# ESP32_breakout.net
KiCad netlist of a schematic drawn in EAGLE
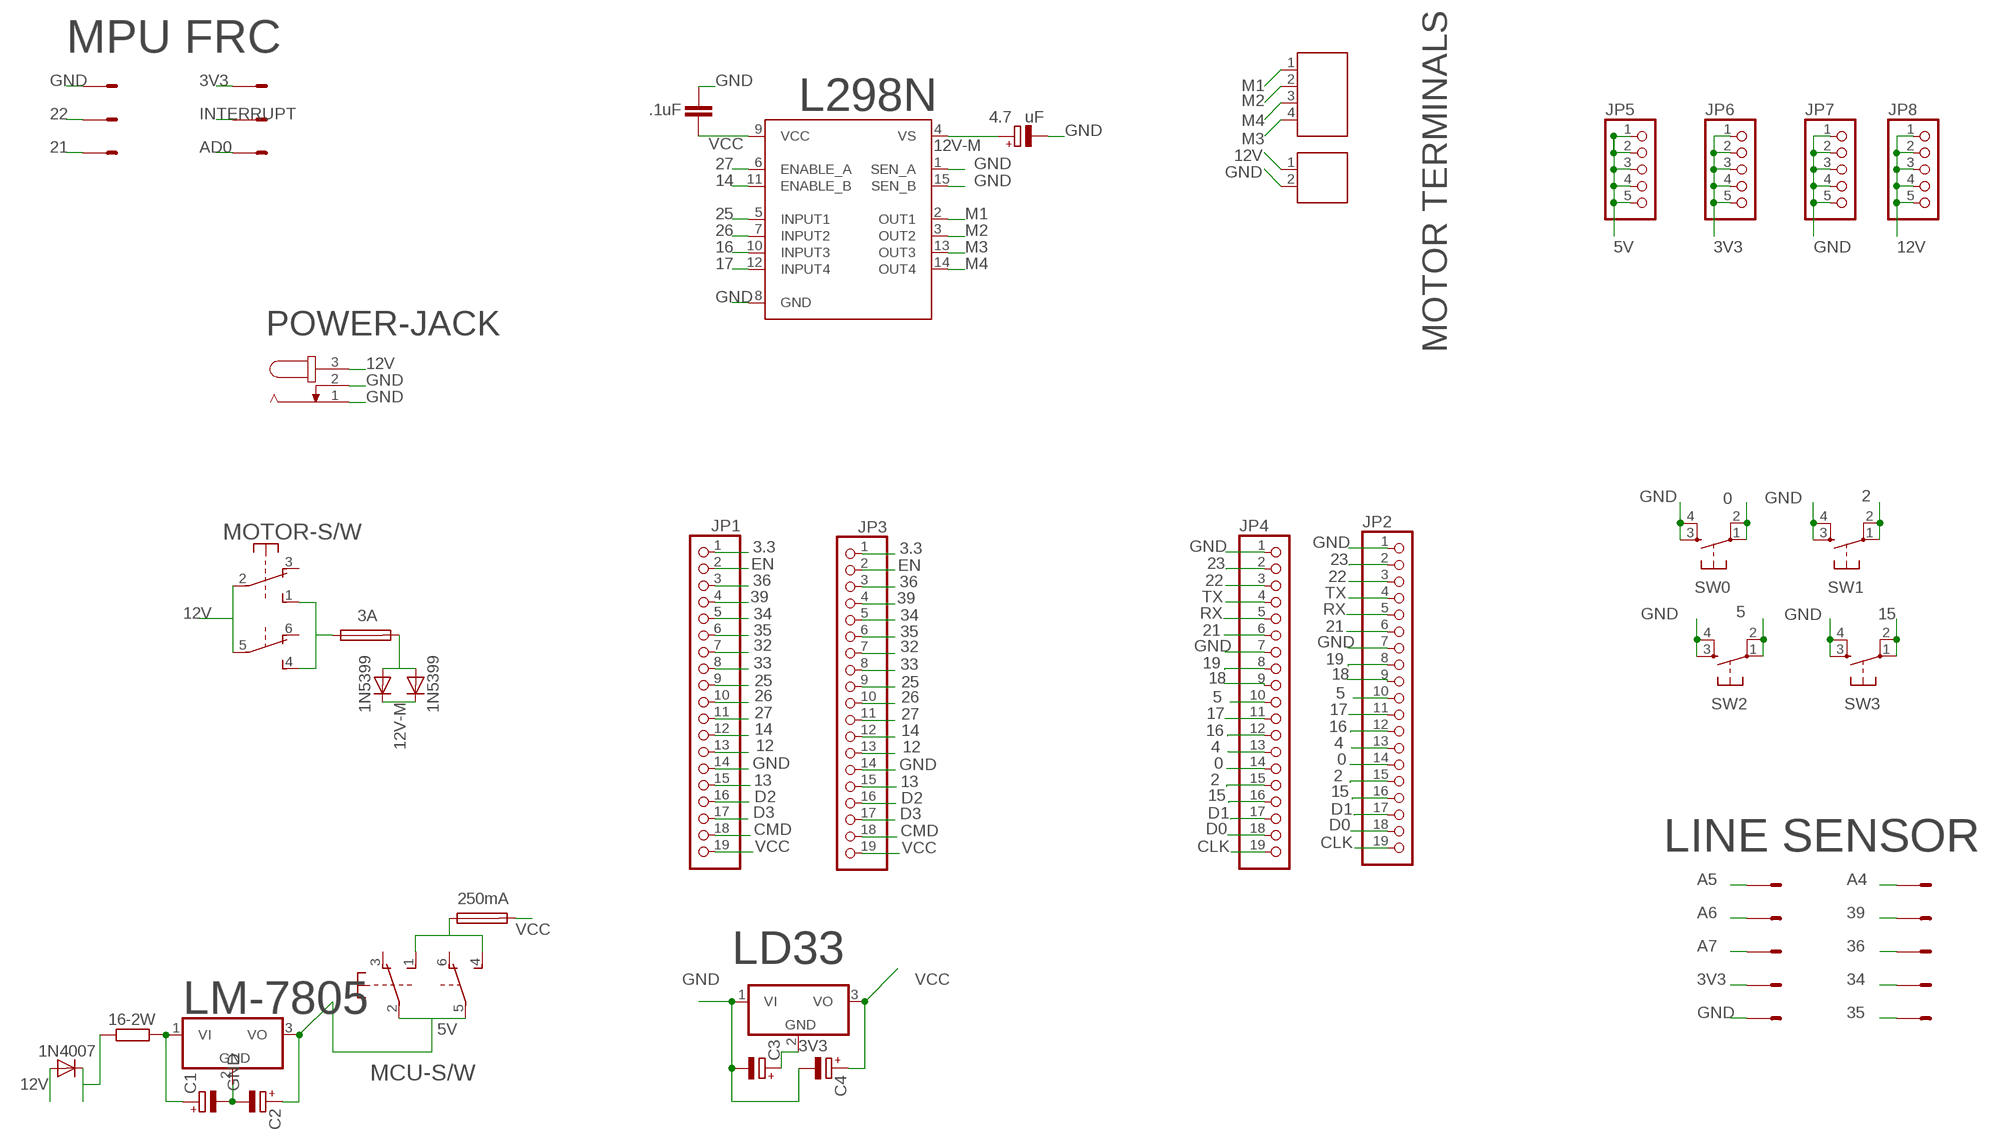
[diagram p0: schematic, sheet 1]

(export (version "E")
  (design (tool "Eeschema 10.0.6"))
  (components
    (comp (ref "12V")
      (value "691131710002")
      (footprint "eagle-import:691131710002")
      (libsource (lib "eagle-import") (part "691131710002"))
    )
    (comp (ref "16-2W")
      (value "R-EU_0617/17")
      (footprint "eagle-import:0617_17")
      (libsource (lib "eagle-import") (part "R-EU_0617/17"))
    )
    (comp (ref "C1")
      (value "CPOL-EUE2.5-6")
      (footprint "eagle-import:E2,5-6")
      (libsource (lib "eagle-import") (part "rcl_334_CPOL-EUE2.5-6"))
    )
    (comp (ref "C2")
      (value "CPOL-EUE2.5-6")
      (footprint "eagle-import:E2,5-6")
      (libsource (lib "eagle-import") (part "rcl_334_CPOL-EUE2.5-6"))
    )
    (comp (ref "C3")
      (value "CPOL-EUE2.5-6")
      (footprint "eagle-import:E2,5-6")
      (libsource (lib "eagle-import") (part "rcl_334_CPOL-EUE2.5-6"))
    )
    (comp (ref "C4")
      (value "CPOL-EUE2.5-6")
      (footprint "eagle-import:E2,5-6")
      (libsource (lib "eagle-import") (part "rcl_334_CPOL-EUE2.5-6"))
    )
    (comp (ref "C8")
      (value "4.7 uF")
      (footprint "eagle-import:E2,5-6")
      (libsource (lib "eagle-import") (part "CPOL-EUE2.5-6"))
    )
    (comp (ref "C9")
      (value ".1uF")
      (footprint "eagle-import:C5B2.5")
      (libsource (lib "eagle-import") (part "C5/2.5"))
    )
    (comp (ref "D4")
      (value "1N4007")
      (footprint "eagle-import:D-7.5")
      (libsource (lib "eagle-import") (part "DIODE-D-7.5"))
    )
    (comp (ref "D6")
      (value "1N5399")
      (footprint "eagle-import:DO15-12")
      (libsource (lib "eagle-import") (part "DIODE-DO15-12"))
    )
    (comp (ref "D7")
      (value "1N5399")
      (footprint "eagle-import:DO15-12")
      (libsource (lib "eagle-import") (part "DIODE-DO15-12"))
    )
    (comp (ref "F1")
      (value "3A")
      (footprint "eagle-import:SH25")
      (fields (field (name "MF") "SCHURTER") (field (name "MPN") "0031.8211"))
      (libsource (lib "eagle-import") (part "SH25"))
    )
    (comp (ref "F2")
      (value "250mA")
      (footprint "eagle-import:SH25")
      (fields (field (name "MF") "SCHURTER") (field (name "MPN") "0031.8211"))
      (libsource (lib "eagle-import") (part "SH25"))
    )
    (comp (ref "J1")
      (value "691131710004")
      (footprint "eagle-import:691131710004")
      (libsource (lib "eagle-import") (part "691131710004"))
    )
    (comp (ref "JP1")
      (value "PINHD-1X19")
      (footprint "eagle-import:1X19")
      (libsource (lib "eagle-import") (part "PINHD-1X19"))
    )
    (comp (ref "JP2")
      (value "PINHD-1X19")
      (footprint "eagle-import:1X19")
      (libsource (lib "eagle-import") (part "PINHD-1X19"))
    )
    (comp (ref "JP3")
      (value "PINHD-1X19")
      (footprint "eagle-import:1X19")
      (libsource (lib "eagle-import") (part "PINHD-1X19"))
    )
    (comp (ref "JP4")
      (value "PINHD-1X19")
      (footprint "eagle-import:1X19")
      (libsource (lib "eagle-import") (part "PINHD-1X19"))
    )
    (comp (ref "JP5")
      (value "PINHD-1X5")
      (footprint "eagle-import:1X05")
      (libsource (lib "eagle-import") (part "PINHD-1X5"))
    )
    (comp (ref "JP6")
      (value "PINHD-1X5")
      (footprint "eagle-import:1X05")
      (libsource (lib "eagle-import") (part "PINHD-1X5"))
    )
    (comp (ref "JP7")
      (value "PINHD-1X5")
      (footprint "eagle-import:1X05")
      (libsource (lib "eagle-import") (part "PINHD-1X5"))
    )
    (comp (ref "JP8")
      (value "PINHD-1X5")
      (footprint "eagle-import:1X05")
      (libsource (lib "eagle-import") (part "PINHD-1X5"))
    )
    (comp (ref "L298N")
      (value "L298")
      (footprint "eagle-import:MULTIWATT-15")
      (fields (field (name "MPN") "L298N"))
      (libsource (lib "eagle-import") (part "L298"))
    )
    (comp (ref "LD33")
      (value "786TV")
      (footprint "eagle-import:TO220V")
      (libsource (lib "eagle-import") (part "78TV6"))
    )
    (comp (ref "LINE-SENSOR")
      (value "057-010-1")
      (footprint "eagle-import:057-010-1")
      (libsource (lib "eagle-import") (part "057-010-1"))
    )
    (comp (ref "LM-7805")
      (value "786TV")
      (footprint "eagle-import:TO220V")
      (libsource (lib "eagle-import") (part "78TV6"))
    )
    (comp (ref "MCU-S/W")
      (value "9077-2")
      (footprint "eagle-import:9077-2")
      (libsource (lib "eagle-import") (part "9077-2"))
    )
    (comp (ref "MOTOR-S/W")
      (value "9077-2")
      (footprint "eagle-import:9077-2")
      (libsource (lib "eagle-import") (part "9077-2"))
    )
    (comp (ref "MPU-6050")
      (value "057-006-1")
      (footprint "eagle-import:057-006-1")
      (libsource (lib "eagle-import") (part "057-006-1"))
    )
    (comp (ref "POWER-JACK")
      (value "JACK-PLUG1")
      (footprint "eagle-import:SPC4078")
      (libsource (lib "eagle-import") (part "JACK-PLUG1"))
    )
    (comp (ref "SW0")
      (value "DTS-6")
      (footprint "eagle-import:DTS-6")
      (libsource (lib "eagle-import") (part "DTS-6"))
    )
    (comp (ref "SW1")
      (value "DTS-6")
      (footprint "eagle-import:DTS-6")
      (libsource (lib "eagle-import") (part "DTS-6"))
    )
    (comp (ref "SW2")
      (value "DTS-6")
      (footprint "eagle-import:DTS-6")
      (libsource (lib "eagle-import") (part "DTS-6"))
    )
    (comp (ref "SW3")
      (value "DTS-6")
      (footprint "eagle-import:DTS-6")
      (libsource (lib "eagle-import") (part "DTS-6"))
    )
  )
  (nets
    (net (code "1") (name "/0") (class "Default")
      (node (ref "JP2") (pin "14") (pinfunction "14_14") (pintype "passive"))
      (node (ref "JP4") (pin "14") (pinfunction "14_14") (pintype "passive"))
      (node (ref "SW0") (pin "1") (pinfunction "1_1") (pintype "passive"))
      (node (ref "SW0") (pin "2") (pinfunction "2_2") (pintype "passive"))
    )
    (net (code "2") (name "/2") (class "Default")
      (node (ref "JP2") (pin "15") (pinfunction "15_15") (pintype "passive"))
      (node (ref "JP4") (pin "15") (pinfunction "15_15") (pintype "passive"))
      (node (ref "SW1") (pin "1") (pinfunction "1_1") (pintype "passive"))
      (node (ref "SW1") (pin "2") (pinfunction "2_2") (pintype "passive"))
    )
    (net (code "3") (name "/3.3") (class "Default")
      (node (ref "JP1") (pin "1") (pinfunction "1_1") (pintype "passive"))
      (node (ref "JP3") (pin "1") (pinfunction "1_1") (pintype "passive"))
    )
    (net (code "4") (name "/3V3") (class "Default")
      (node (ref "C3") (pin "+") (pinfunction "+_+") (pintype "passive"))
      (node (ref "JP6") (pin "1") (pinfunction "1_1") (pintype "passive"))
      (node (ref "JP6") (pin "2") (pinfunction "2_2") (pintype "passive"))
      (node (ref "JP6") (pin "3") (pinfunction "3_3") (pintype "passive"))
      (node (ref "JP6") (pin "4") (pinfunction "4_4") (pintype "passive"))
      (node (ref "JP6") (pin "5") (pinfunction "5_5") (pintype "passive"))
      (node (ref "LD33") (pin "2") (pinfunction "GND_2") (pintype "passive"))
      (node (ref "LINE-SENSOR") (pin "7") (pinfunction "S_7") (pintype "passive"))
      (node (ref "MPU-6050") (pin "2") (pinfunction "S_2") (pintype "passive"))
    )
    (net (code "5") (name "/4") (class "Default")
      (node (ref "JP2") (pin "13") (pinfunction "13_13") (pintype "passive"))
      (node (ref "JP4") (pin "13") (pinfunction "13_13") (pintype "passive"))
    )
    (net (code "6") (name "/5") (class "Default")
      (node (ref "JP2") (pin "10") (pinfunction "10_10") (pintype "passive"))
      (node (ref "JP4") (pin "10") (pinfunction "10_10") (pintype "passive"))
      (node (ref "SW2") (pin "1") (pinfunction "1_1") (pintype "passive"))
      (node (ref "SW2") (pin "2") (pinfunction "2_2") (pintype "passive"))
    )
    (net (code "7") (name "/5V") (class "Default")
      (node (ref "C2") (pin "+") (pinfunction "+_+") (pintype "passive"))
      (node (ref "JP5") (pin "1") (pinfunction "1_1") (pintype "passive"))
      (node (ref "JP5") (pin "2") (pinfunction "2_2") (pintype "passive"))
      (node (ref "JP5") (pin "3") (pinfunction "3_3") (pintype "passive"))
      (node (ref "JP5") (pin "4") (pinfunction "4_4") (pintype "passive"))
      (node (ref "JP5") (pin "5") (pinfunction "5_5") (pintype "passive"))
      (node (ref "LM-7805") (pin "3") (pinfunction "VO_3") (pintype "passive"))
      (node (ref "MCU-S/W") (pin "2") (pinfunction "P_2") (pintype "passive"))
      (node (ref "MCU-S/W") (pin "5") (pinfunction "P_5") (pintype "passive"))
    )
    (net (code "8") (name "/12") (class "Default")
      (node (ref "JP1") (pin "13") (pinfunction "13_13") (pintype "passive"))
      (node (ref "JP3") (pin "13") (pinfunction "13_13") (pintype "passive"))
    )
    (net (code "9") (name "/12V") (class "Default")
      (node (ref "12V") (pin "1") (pinfunction "1_1") (pintype "passive"))
      (node (ref "D4") (pin "A") (pinfunction "A_A") (pintype "passive"))
      (node (ref "JP8") (pin "1") (pinfunction "1_1") (pintype "passive"))
      (node (ref "JP8") (pin "2") (pinfunction "2_2") (pintype "passive"))
      (node (ref "JP8") (pin "3") (pinfunction "3_3") (pintype "passive"))
      (node (ref "JP8") (pin "4") (pinfunction "4_4") (pintype "passive"))
      (node (ref "JP8") (pin "5") (pinfunction "5_5") (pintype "passive"))
      (node (ref "MOTOR-S/W") (pin "2") (pinfunction "P_2") (pintype "passive"))
      (node (ref "MOTOR-S/W") (pin "5") (pinfunction "P_5") (pintype "passive"))
      (node (ref "POWER-JACK") (pin "3") (pinfunction "3_3") (pintype "passive"))
    )
    (net (code "10") (name "/12V-M") (class "Default")
      (node (ref "C8") (pin "+") (pinfunction "+_+") (pintype "passive"))
      (node (ref "D6") (pin "C") (pinfunction "C_C") (pintype "passive"))
      (node (ref "D7") (pin "C") (pinfunction "C_C") (pintype "passive"))
      (node (ref "L298N") (pin "4") (pinfunction "VS_4") (pintype "power_in"))
    )
    (net (code "11") (name "/13") (class "Default")
      (node (ref "JP1") (pin "15") (pinfunction "15_15") (pintype "passive"))
      (node (ref "JP3") (pin "15") (pinfunction "15_15") (pintype "passive"))
    )
    (net (code "12") (name "/14") (class "Default")
      (node (ref "JP1") (pin "12") (pinfunction "12_12") (pintype "passive"))
      (node (ref "JP3") (pin "12") (pinfunction "12_12") (pintype "passive"))
      (node (ref "L298N") (pin "11") (pinfunction "ENABLE_B_11") (pintype "input"))
    )
    (net (code "13") (name "/15") (class "Default")
      (node (ref "JP2") (pin "16") (pinfunction "16_16") (pintype "passive"))
      (node (ref "JP4") (pin "16") (pinfunction "16_16") (pintype "passive"))
      (node (ref "SW3") (pin "1") (pinfunction "1_1") (pintype "passive"))
      (node (ref "SW3") (pin "2") (pinfunction "2_2") (pintype "passive"))
    )
    (net (code "14") (name "/16") (class "Default")
      (node (ref "JP2") (pin "12") (pinfunction "12_12") (pintype "passive"))
      (node (ref "JP4") (pin "12") (pinfunction "12_12") (pintype "passive"))
      (node (ref "L298N") (pin "10") (pinfunction "INPUT3_10") (pintype "input"))
    )
    (net (code "15") (name "/17") (class "Default")
      (node (ref "JP2") (pin "11") (pinfunction "11_11") (pintype "passive"))
      (node (ref "JP4") (pin "11") (pinfunction "11_11") (pintype "passive"))
      (node (ref "L298N") (pin "12") (pinfunction "INPUT4_12") (pintype "input"))
    )
    (net (code "16") (name "/18") (class "Default")
      (node (ref "JP2") (pin "9") (pinfunction "9_9") (pintype "passive"))
      (node (ref "JP4") (pin "9") (pinfunction "9_9") (pintype "passive"))
    )
    (net (code "17") (name "/19") (class "Default")
      (node (ref "JP2") (pin "8") (pinfunction "8_8") (pintype "passive"))
      (node (ref "JP4") (pin "8") (pinfunction "8_8") (pintype "passive"))
    )
    (net (code "18") (name "/21") (class "Default")
      (node (ref "JP2") (pin "6") (pinfunction "6_6") (pintype "passive"))
      (node (ref "JP4") (pin "6") (pinfunction "6_6") (pintype "passive"))
      (node (ref "MPU-6050") (pin "5") (pinfunction "S_5") (pintype "passive"))
    )
    (net (code "19") (name "/22") (class "Default")
      (node (ref "JP2") (pin "3") (pinfunction "3_3") (pintype "passive"))
      (node (ref "JP4") (pin "3") (pinfunction "3_3") (pintype "passive"))
      (node (ref "MPU-6050") (pin "3") (pinfunction "S_3") (pintype "passive"))
    )
    (net (code "20") (name "/23") (class "Default")
      (node (ref "JP2") (pin "2") (pinfunction "2_2") (pintype "passive"))
      (node (ref "JP4") (pin "2") (pinfunction "2_2") (pintype "passive"))
    )
    (net (code "21") (name "/25") (class "Default")
      (node (ref "JP1") (pin "9") (pinfunction "9_9") (pintype "passive"))
      (node (ref "JP3") (pin "9") (pinfunction "9_9") (pintype "passive"))
      (node (ref "L298N") (pin "5") (pinfunction "INPUT1_5") (pintype "input"))
    )
    (net (code "22") (name "/26") (class "Default")
      (node (ref "JP1") (pin "10") (pinfunction "10_10") (pintype "passive"))
      (node (ref "JP3") (pin "10") (pinfunction "10_10") (pintype "passive"))
      (node (ref "L298N") (pin "7") (pinfunction "INPUT2_7") (pintype "input"))
    )
    (net (code "23") (name "/27") (class "Default")
      (node (ref "JP1") (pin "11") (pinfunction "11_11") (pintype "passive"))
      (node (ref "JP3") (pin "11") (pinfunction "11_11") (pintype "passive"))
      (node (ref "L298N") (pin "6") (pinfunction "ENABLE_A_6") (pintype "input"))
    )
    (net (code "24") (name "/32") (class "Default")
      (node (ref "JP1") (pin "7") (pinfunction "7_7") (pintype "passive"))
      (node (ref "JP3") (pin "7") (pinfunction "7_7") (pintype "passive"))
    )
    (net (code "25") (name "/33") (class "Default")
      (node (ref "JP1") (pin "8") (pinfunction "8_8") (pintype "passive"))
      (node (ref "JP3") (pin "8") (pinfunction "8_8") (pintype "passive"))
    )
    (net (code "26") (name "/34") (class "Default")
      (node (ref "JP1") (pin "5") (pinfunction "5_5") (pintype "passive"))
      (node (ref "JP3") (pin "5") (pinfunction "5_5") (pintype "passive"))
      (node (ref "LINE-SENSOR") (pin "8") (pinfunction "S_8") (pintype "passive"))
    )
    (net (code "27") (name "/35") (class "Default")
      (node (ref "JP1") (pin "6") (pinfunction "6_6") (pintype "passive"))
      (node (ref "JP3") (pin "6") (pinfunction "6_6") (pintype "passive"))
      (node (ref "LINE-SENSOR") (pin "10") (pinfunction "S_10") (pintype "passive"))
    )
    (net (code "28") (name "/36") (class "Default")
      (node (ref "JP1") (pin "3") (pinfunction "3_3") (pintype "passive"))
      (node (ref "JP3") (pin "3") (pinfunction "3_3") (pintype "passive"))
      (node (ref "LINE-SENSOR") (pin "6") (pinfunction "S_6") (pintype "passive"))
    )
    (net (code "29") (name "/39") (class "Default")
      (node (ref "JP1") (pin "4") (pinfunction "4_4") (pintype "passive"))
      (node (ref "JP3") (pin "4") (pinfunction "4_4") (pintype "passive"))
      (node (ref "LINE-SENSOR") (pin "4") (pinfunction "S_4") (pintype "passive"))
    )
    (net (code "30") (name "/A4") (class "Default")
      (node (ref "LINE-SENSOR") (pin "2") (pinfunction "S_2") (pintype "passive"))
    )
    (net (code "31") (name "/A5") (class "Default")
      (node (ref "LINE-SENSOR") (pin "1") (pinfunction "S_1") (pintype "passive"))
    )
    (net (code "32") (name "/A6") (class "Default")
      (node (ref "LINE-SENSOR") (pin "3") (pinfunction "S_3") (pintype "passive"))
    )
    (net (code "33") (name "/A7") (class "Default")
      (node (ref "LINE-SENSOR") (pin "5") (pinfunction "S_5") (pintype "passive"))
    )
    (net (code "34") (name "/CLK") (class "Default")
      (node (ref "JP2") (pin "19") (pinfunction "19_19") (pintype "passive"))
      (node (ref "JP4") (pin "19") (pinfunction "19_19") (pintype "passive"))
    )
    (net (code "35") (name "/CMD") (class "Default")
      (node (ref "JP1") (pin "18") (pinfunction "18_18") (pintype "passive"))
      (node (ref "JP3") (pin "18") (pinfunction "18_18") (pintype "passive"))
    )
    (net (code "36") (name "/D0") (class "Default")
      (node (ref "JP2") (pin "18") (pinfunction "18_18") (pintype "passive"))
      (node (ref "JP4") (pin "18") (pinfunction "18_18") (pintype "passive"))
    )
    (net (code "37") (name "/D1") (class "Default")
      (node (ref "JP2") (pin "17") (pinfunction "17_17") (pintype "passive"))
      (node (ref "JP4") (pin "17") (pinfunction "17_17") (pintype "passive"))
    )
    (net (code "38") (name "/D2") (class "Default")
      (node (ref "JP1") (pin "16") (pinfunction "16_16") (pintype "passive"))
      (node (ref "JP3") (pin "16") (pinfunction "16_16") (pintype "passive"))
    )
    (net (code "39") (name "/D3") (class "Default")
      (node (ref "JP1") (pin "17") (pinfunction "17_17") (pintype "passive"))
      (node (ref "JP3") (pin "17") (pinfunction "17_17") (pintype "passive"))
    )
    (net (code "40") (name "/EN") (class "Default")
      (node (ref "JP1") (pin "2") (pinfunction "2_2") (pintype "passive"))
      (node (ref "JP3") (pin "2") (pinfunction "2_2") (pintype "passive"))
    )
    (net (code "41") (name "/GND") (class "Default")
      (node (ref "12V") (pin "2") (pinfunction "2_2") (pintype "passive"))
      (node (ref "C1") (pin "-") (pinfunction "-_-") (pintype "passive"))
      (node (ref "C2") (pin "-") (pinfunction "-_-") (pintype "passive"))
      (node (ref "C3") (pin "-") (pinfunction "-_-") (pintype "passive"))
      (node (ref "C4") (pin "-") (pinfunction "-_-") (pintype "passive"))
      (node (ref "C8") (pin "-") (pinfunction "-_-") (pintype "passive"))
      (node (ref "C9") (pin "2") (pinfunction "2_2") (pintype "passive"))
      (node (ref "JP1") (pin "14") (pinfunction "14_14") (pintype "passive"))
      (node (ref "JP2") (pin "1") (pinfunction "1_1") (pintype "passive"))
      (node (ref "JP2") (pin "7") (pinfunction "7_7") (pintype "passive"))
      (node (ref "JP3") (pin "14") (pinfunction "14_14") (pintype "passive"))
      (node (ref "JP4") (pin "1") (pinfunction "1_1") (pintype "passive"))
      (node (ref "JP4") (pin "7") (pinfunction "7_7") (pintype "passive"))
      (node (ref "JP7") (pin "1") (pinfunction "1_1") (pintype "passive"))
      (node (ref "JP7") (pin "2") (pinfunction "2_2") (pintype "passive"))
      (node (ref "JP7") (pin "3") (pinfunction "3_3") (pintype "passive"))
      (node (ref "JP7") (pin "4") (pinfunction "4_4") (pintype "passive"))
      (node (ref "JP7") (pin "5") (pinfunction "5_5") (pintype "passive"))
      (node (ref "L298N") (pin "1") (pinfunction "SEN_A_1") (pintype "input"))
      (node (ref "L298N") (pin "15") (pinfunction "SEN_B_15") (pintype "input"))
      (node (ref "L298N") (pin "8") (pinfunction "GND_8") (pintype "power_in"))
      (node (ref "LD33") (pin "1") (pinfunction "VI_1") (pintype "input"))
      (node (ref "LINE-SENSOR") (pin "9") (pinfunction "S_9") (pintype "passive"))
      (node (ref "LM-7805") (pin "2") (pinfunction "GND_2") (pintype "passive"))
      (node (ref "MPU-6050") (pin "1") (pinfunction "S_1") (pintype "passive"))
      (node (ref "MPU-6050") (pin "6") (pinfunction "S_6") (pintype "passive"))
      (node (ref "POWER-JACK") (pin "1") (pinfunction "1_1") (pintype "passive"))
      (node (ref "POWER-JACK") (pin "2") (pinfunction "2_2") (pintype "passive"))
      (node (ref "SW0") (pin "3") (pinfunction "3_3") (pintype "passive"))
      (node (ref "SW0") (pin "4") (pinfunction "4_4") (pintype "passive"))
      (node (ref "SW1") (pin "3") (pinfunction "3_3") (pintype "passive"))
      (node (ref "SW1") (pin "4") (pinfunction "4_4") (pintype "passive"))
      (node (ref "SW2") (pin "3") (pinfunction "3_3") (pintype "passive"))
      (node (ref "SW2") (pin "4") (pinfunction "4_4") (pintype "passive"))
      (node (ref "SW3") (pin "3") (pinfunction "3_3") (pintype "passive"))
      (node (ref "SW3") (pin "4") (pinfunction "4_4") (pintype "passive"))
    )
    (net (code "42") (name "/INTERRUPT") (class "Default")
      (node (ref "MPU-6050") (pin "4") (pinfunction "S_4") (pintype "passive"))
    )
    (net (code "43") (name "/M1") (class "Default")
      (node (ref "J1") (pin "1") (pinfunction "1_1") (pintype "passive"))
      (node (ref "L298N") (pin "2") (pinfunction "OUT1_2") (pintype "output"))
    )
    (net (code "44") (name "/M2") (class "Default")
      (node (ref "J1") (pin "2") (pinfunction "2_2") (pintype "passive"))
      (node (ref "L298N") (pin "3") (pinfunction "OUT2_3") (pintype "output"))
    )
    (net (code "45") (name "/M3") (class "Default")
      (node (ref "J1") (pin "4") (pinfunction "4_4") (pintype "passive"))
      (node (ref "L298N") (pin "13") (pinfunction "OUT3_13") (pintype "output"))
    )
    (net (code "46") (name "/M4") (class "Default")
      (node (ref "J1") (pin "3") (pinfunction "3_3") (pintype "passive"))
      (node (ref "L298N") (pin "14") (pinfunction "OUT4_14") (pintype "output"))
    )
    (net (code "47") (name "/RX") (class "Default")
      (node (ref "JP2") (pin "5") (pinfunction "5_5") (pintype "passive"))
      (node (ref "JP4") (pin "5") (pinfunction "5_5") (pintype "passive"))
    )
    (net (code "48") (name "/TX") (class "Default")
      (node (ref "JP2") (pin "4") (pinfunction "4_4") (pintype "passive"))
      (node (ref "JP4") (pin "4") (pinfunction "4_4") (pintype "passive"))
    )
    (net (code "49") (name "/VCC") (class "Default")
      (node (ref "C4") (pin "+") (pinfunction "+_+") (pintype "passive"))
      (node (ref "C9") (pin "1") (pinfunction "1_1") (pintype "passive"))
      (node (ref "F2") (pin "2") (pinfunction "2_2") (pintype "passive"))
      (node (ref "JP1") (pin "19") (pinfunction "19_19") (pintype "passive"))
      (node (ref "JP3") (pin "19") (pinfunction "19_19") (pintype "passive"))
      (node (ref "L298N") (pin "9") (pinfunction "VCC_9") (pintype "power_in"))
      (node (ref "LD33") (pin "3") (pinfunction "VO_3") (pintype "passive"))
    )
    (net (code "50") (name "Net-(16-2W-Pad1)") (class "Default")
      (node (ref "16-2W") (pin "1") (pinfunction "1_1") (pintype "passive"))
      (node (ref "D4") (pin "C") (pinfunction "C_C") (pintype "passive"))
    )
    (net (code "51") (name "Net-(D6-PadA)") (class "Default")
      (node (ref "D6") (pin "A") (pinfunction "A_A") (pintype "passive"))
      (node (ref "D7") (pin "A") (pinfunction "A_A") (pintype "passive"))
      (node (ref "F1") (pin "2") (pinfunction "2_2") (pintype "passive"))
    )
    (net (code "52") (name "Net-(LM-7805-VI)") (class "Default")
      (node (ref "16-2W") (pin "2") (pinfunction "2_2") (pintype "passive"))
      (node (ref "C1") (pin "+") (pinfunction "+_+") (pintype "passive"))
      (node (ref "LM-7805") (pin "1") (pinfunction "VI_1") (pintype "input"))
    )
    (net (code "53") (name "Net-(MCU-S/WA-S)") (class "Default")
      (node (ref "F2") (pin "1") (pinfunction "1_1") (pintype "passive"))
      (node (ref "MCU-S/W") (pin "1") (pinfunction "S_1") (pintype "passive"))
      (node (ref "MCU-S/W") (pin "4") (pinfunction "S_4") (pintype "passive"))
    )
    (net (code "54") (name "Net-(MOTOR-S/WA-S)") (class "Default")
      (node (ref "F1") (pin "1") (pinfunction "1_1") (pintype "passive"))
      (node (ref "MOTOR-S/W") (pin "1") (pinfunction "S_1") (pintype "passive"))
      (node (ref "MOTOR-S/W") (pin "4") (pinfunction "S_4") (pintype "passive"))
    )
    (net (code "55") (name "unconnected-(MCU-S/WA-O-Pad3)") (class "Default")
      (node (ref "MCU-S/W") (pin "3") (pinfunction "O_3") (pintype "passive"))
    )
    (net (code "56") (name "unconnected-(MCU-S/WB-O-Pad6)") (class "Default")
      (node (ref "MCU-S/W") (pin "6") (pinfunction "O_6") (pintype "passive"))
    )
    (net (code "57") (name "unconnected-(MOTOR-S/WA-O-Pad3)") (class "Default")
      (node (ref "MOTOR-S/W") (pin "3") (pinfunction "O_3") (pintype "passive"))
    )
    (net (code "58") (name "unconnected-(MOTOR-S/WB-O-Pad6)") (class "Default")
      (node (ref "MOTOR-S/W") (pin "6") (pinfunction "O_6") (pintype "passive"))
    )
  )
)
